# HV_DAC_8ch_References.net
KiCad netlist of a schematic drawn in Altium Designer
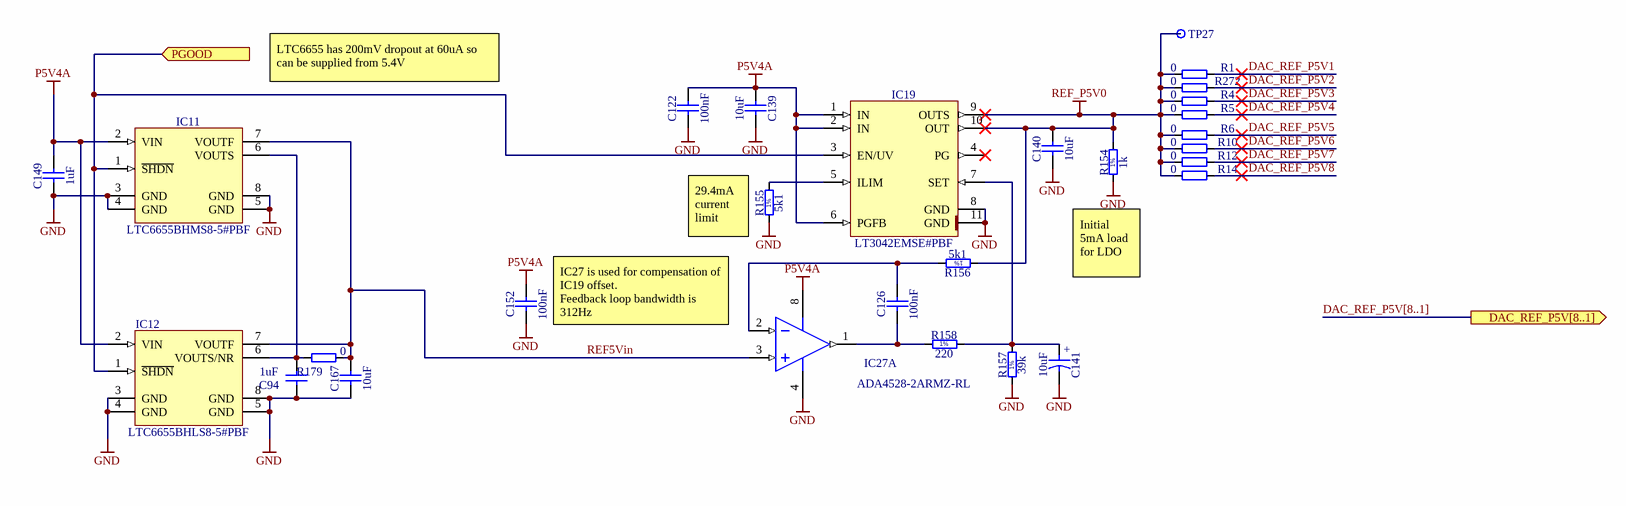
[diagram p0: HV_DAC_8ch_References.SchDoc]

(export (version "E")
  (design (tool "Eeschema 10.0.6"))
  (components
    (comp (ref "C94")
      (value "1uF")
      (footprint "CAPC1608X87N")
      (description "Non-polarised capacitor")
      (fields
        (field (name "PART NUMBER") "CC0603_1UF_25V_10%_X7R")
        (field (name "VOLTAGE") "25V")
        (field (name "AUTHOR") "CERN DEM JLC")
      )
      (libsource (lib "Capacitors") (part "Capacitor - non polarized"))
    )
    (comp (ref "C122")
      (value "100nF")
      (footprint "CAPC1005X55N")
      (description "Non-polarised capacitor")
      (fields
        (field (name "PART NUMBER") "CC0402_100NF_16V_10%_X5R")
        (field (name "VOLTAGE") "16V")
        (field (name "AUTHOR") "CERN DEM JLC")
      )
      (libsource (lib "Capacitors") (part "Capacitor - non polarized"))
    )
    (comp (ref "C126")
      (value "100nF")
      (footprint "CAPC1005X55N")
      (description "Non-polarised capacitor")
      (fields
        (field (name "PART NUMBER") "CC0402_100NF_16V_10%_X5R")
        (field (name "VOLTAGE") "16V")
        (field (name "AUTHOR") "CERN DEM JLC")
      )
      (libsource (lib "Capacitors") (part "Capacitor - non polarized"))
    )
    (comp (ref "C139")
      (value "10uF")
      (footprint "CAPC1608X80N")
      (description "Non-polarised capacitor")
      (fields
        (field (name "PART NUMBER") "CC0603_10UF_10V_10%_X5R")
        (field (name "VOLTAGE") "10V")
        (field (name "AUTHOR") "CERN DEM JLC")
      )
      (libsource (lib "Capacitors") (part "Capacitor - non polarized"))
    )
    (comp (ref "C140")
      (value "10uF")
      (footprint "CAPC1608X80N")
      (description "Non-polarised capacitor")
      (fields
        (field (name "PART NUMBER") "CC0603_10UF_10V_10%_X5R")
        (field (name "VOLTAGE") "10V")
        (field (name "AUTHOR") "CERN DEM JLC")
      )
      (libsource (lib "Capacitors") (part "Capacitor - non polarized"))
    )
    (comp (ref "C141")
      (value "10uF")
      (footprint "CAPMP3216X180N")
      (description "Polarised capacitor")
      (fields
        (field (name "PART NUMBER") "CTE3216-18_10UF_16V_20%_AVX_TCJ")
        (field (name "VOLTAGE") "16V")
        (field (name "AUTHOR") "CERN DEM JLC")
      )
      (libsource (lib "Capacitors") (part "Capacitor - polarized"))
    )
    (comp (ref "C149")
      (value "1uF")
      (footprint "CAPC1608X87N")
      (description "Non-polarised capacitor")
      (fields
        (field (name "PART NUMBER") "CC0603_1UF_25V_10%_X7R")
        (field (name "VOLTAGE") "25V")
        (field (name "AUTHOR") "CERN DEM JLC")
      )
      (libsource (lib "Capacitors") (part "Capacitor - non polarized"))
    )
    (comp (ref "C152")
      (value "100nF")
      (footprint "CAPC1005X55N")
      (description "Non-polarised capacitor")
      (fields
        (field (name "PART NUMBER") "CC0402_100NF_16V_10%_X5R")
        (field (name "VOLTAGE") "16V")
        (field (name "AUTHOR") "CERN DEM JLC")
      )
      (libsource (lib "Capacitors") (part "Capacitor - non polarized"))
    )
    (comp (ref "C167")
      (value "10uF")
      (footprint "CAPC1608X80N")
      (description "Non-polarised capacitor")
      (fields
        (field (name "PART NUMBER") "CC0603_10UF_10V_10%_X5R")
        (field (name "VOLTAGE") "10V")
        (field (name "AUTHOR") "CERN DEM JLC")
      )
      (libsource (lib "Capacitors") (part "Capacitor - non polarized"))
    )
    (comp (ref "IC11")
      (value "LTC6655BHMS8-5#PBF")
      (footprint "SOP65P490X110-8N")
      (description "0.25ppm Noise, Low Drift Precision Buffered Voltage Reference")
      (fields (field (name "MANUFACTURER") "LINEAR TECHNOLOGY") (field (name "AUTHOR") "CERN DEM JLC"))
      (libsource (lib "ICs And Semiconductors") (part "LTC6655"))
    )
    (comp (ref "IC12")
      (value "LTC6655BHLS8-5#PBF")
      (footprint "8-CLCC")
      (description "5.0V, 1uA Precision Voltage Reference")
      (fields (field (name "MANUFACTURER") "LINEAR TECHNOLOGY") (field (name "AUTHOR") "GK"))
      (libsource (lib "Sampler") (part "REF_LTC6655CHLS8-4.096"))
    )
    (comp (ref "IC19")
      (value "LT3042EMSE#PBF")
      (footprint "SOP50P490X110-11N-R168X198")
      (description "20V, 200mA, Ultralow Noise, Ultrahigh PSRR RF Linear Regulator")
      (fields (field (name "MANUFACTURER") "LINEAR TECHNOLOGY") (field (name "AUTHOR") "CERN DEM MR"))
      (libsource (lib "ICs And Semiconductors") (part "LT3042"))
    )
    (comp (ref "IC27")
      (value "ADA4528-2ARMZ-RL")
      (footprint "ADI-RM-8_N")
      (fields (field (name "GENERIC PART NUMBER") "ADA4528-2") (field (name "MANUFACTURER") "Analog Devices"))
      (libsource (lib "Altium Content Vault") (part "ADI-ADA4000-2-X-8"))
    )
    (comp (ref "R1")
      (value "0")
      (footprint "RESC1005X40N")
      (description "Resistor")
      (fields
        (field (name "PART NUMBER") "R0402_0R_JUMPER")
        (field (name "MANUFACTURER") "GENERIC")
        (field (name "AUTHOR") "CERN DEM JLC")
      )
      (libsource (lib "Resistors") (part "Resistor"))
    )
    (comp (ref "R4")
      (value "0")
      (footprint "RESC1005X40N")
      (description "Resistor")
      (fields
        (field (name "PART NUMBER") "R0402_0R_JUMPER")
        (field (name "MANUFACTURER") "GENERIC")
        (field (name "AUTHOR") "CERN DEM JLC")
      )
      (libsource (lib "Resistors") (part "Resistor"))
    )
    (comp (ref "R5")
      (value "0")
      (footprint "RESC1005X40N")
      (description "Resistor")
      (fields
        (field (name "PART NUMBER") "R0402_0R_JUMPER")
        (field (name "MANUFACTURER") "GENERIC")
        (field (name "AUTHOR") "CERN DEM JLC")
      )
      (libsource (lib "Resistors") (part "Resistor"))
    )
    (comp (ref "R6")
      (value "0")
      (footprint "RESC1005X40N")
      (description "Resistor")
      (fields
        (field (name "PART NUMBER") "R0402_0R_JUMPER")
        (field (name "MANUFACTURER") "GENERIC")
        (field (name "AUTHOR") "CERN DEM JLC")
      )
      (libsource (lib "Resistors") (part "Resistor"))
    )
    (comp (ref "R10")
      (value "0")
      (footprint "RESC1005X40N")
      (description "Resistor")
      (fields
        (field (name "PART NUMBER") "R0402_0R_JUMPER")
        (field (name "MANUFACTURER") "GENERIC")
        (field (name "AUTHOR") "CERN DEM JLC")
      )
      (libsource (lib "Resistors") (part "Resistor"))
    )
    (comp (ref "R12")
      (value "0")
      (footprint "RESC1005X40N")
      (description "Resistor")
      (fields
        (field (name "PART NUMBER") "R0402_0R_JUMPER")
        (field (name "MANUFACTURER") "GENERIC")
        (field (name "AUTHOR") "CERN DEM JLC")
      )
      (libsource (lib "Resistors") (part "Resistor"))
    )
    (comp (ref "R14")
      (value "0")
      (footprint "RESC1005X40N")
      (description "Resistor")
      (fields
        (field (name "PART NUMBER") "R0402_0R_JUMPER")
        (field (name "MANUFACTURER") "GENERIC")
        (field (name "AUTHOR") "CERN DEM JLC")
      )
      (libsource (lib "Resistors") (part "Resistor"))
    )
    (comp (ref "R154")
      (value "1k")
      (footprint "RESC1005X40N")
      (description "Resistor - 1%")
      (fields
        (field (name "PART NUMBER") "R0402_1K_1%_0.0625W_100PPM")
        (field (name "POWER") "0.0625W")
        (field (name "AUTHOR") "CERN DEM JLC")
      )
      (libsource (lib "Resistors") (part "Resistor - 1%"))
    )
    (comp (ref "R155")
      (value "5k1")
      (footprint "RESC1005X40N")
      (description "Resistor - 1%")
      (fields
        (field (name "PART NUMBER") "R0402_5K1_1%_0.0625W_100PPM")
        (field (name "POWER") "0.0625W")
        (field (name "AUTHOR") "CERN DEM JLC")
      )
      (libsource (lib "Resistors") (part "Resistor - 1%"))
    )
    (comp (ref "R156")
      (value "5k1")
      (footprint "RESC1005X40N")
      (description "Resistor - 1%")
      (fields
        (field (name "PART NUMBER") "R0402_5K1_1%_0.0625W_100PPM")
        (field (name "POWER") "0.0625W")
        (field (name "AUTHOR") "CERN DEM JLC")
      )
      (libsource (lib "Resistors") (part "Resistor - 1%"))
    )
    (comp (ref "R157")
      (value "39k")
      (footprint "RESC1608X55N")
      (description "Resistor - 1%")
      (fields
        (field (name "PART NUMBER") "R0603_39K_1%_0.1W_100PPM")
        (field (name "POWER") "0.1W")
        (field (name "AUTHOR") "CERN DEM JLC")
      )
      (libsource (lib "Resistors") (part "Resistor - 1%"))
    )
    (comp (ref "R158")
      (value "220")
      (footprint "RESC1005X40N")
      (description "Resistor - 1%")
      (fields
        (field (name "PART NUMBER") "R0402_220R_1%_0.0625W_100PPM")
        (field (name "POWER") "0.0625W")
        (field (name "AUTHOR") "CERN DEM JLC")
      )
      (libsource (lib "Resistors") (part "Resistor - 1%"))
    )
    (comp (ref "R179")
      (value "0")
      (footprint "RESC1005X40N")
      (description "Resistor")
      (fields
        (field (name "PART NUMBER") "R0402_0R_JUMPER")
        (field (name "MANUFACTURER") "GENERIC")
        (field (name "AUTHOR") "CERN DEM JLC")
      )
      (libsource (lib "Resistors") (part "Resistor"))
    )
    (comp (ref "R272")
      (value "0")
      (footprint "RESC1005X40N")
      (description "Resistor")
      (fields
        (field (name "PART NUMBER") "R0402_0R_JUMPER")
        (field (name "MANUFACTURER") "GENERIC")
        (field (name "AUTHOR") "CERN DEM JLC")
      )
      (libsource (lib "Resistors") (part "Resistor"))
    )
    (comp (ref "TP27")
      (value "Test Point")
      (footprint "TPS127")
      (fields (field (name "PART NUMBER") "SMD_PAD_1.27X1.27MM") (field (name "AUTHOR") "CERN DEM JLC"))
      (libsource (lib "Eletro-mechanical") (part "Test Point"))
    )
  )
  (nets
    (net (code "1") (name "/DAC_REF_P5V1") (class "Default")
      (node (ref "R1") (pin "2") (pinfunction "2_2") (pintype "passive"))
    )
    (net (code "2") (name "/DAC_REF_P5V2") (class "Default")
      (node (ref "R272") (pin "2") (pinfunction "2_2") (pintype "passive"))
    )
    (net (code "3") (name "/DAC_REF_P5V3") (class "Default")
      (node (ref "R4") (pin "2") (pinfunction "2_2") (pintype "passive"))
    )
    (net (code "4") (name "/DAC_REF_P5V4") (class "Default")
      (node (ref "R5") (pin "2") (pinfunction "2_2") (pintype "passive"))
    )
    (net (code "5") (name "/DAC_REF_P5V5") (class "Default")
      (node (ref "R6") (pin "2") (pinfunction "2_2") (pintype "passive"))
    )
    (net (code "6") (name "/DAC_REF_P5V6") (class "Default")
      (node (ref "R10") (pin "2") (pinfunction "2_2") (pintype "passive"))
    )
    (net (code "7") (name "/DAC_REF_P5V7") (class "Default")
      (node (ref "R12") (pin "2") (pinfunction "2_2") (pintype "passive"))
    )
    (net (code "8") (name "/DAC_REF_P5V8") (class "Default")
      (node (ref "R14") (pin "2") (pinfunction "2_2") (pintype "passive"))
    )
    (net (code "10") (name "/PGOOD") (class "Default")
      (node (ref "IC11") (pin "1") (pinfunction "~{SHDN}_1") (pintype "input"))
      (node (ref "IC12") (pin "1") (pinfunction "~{SHDN}_1") (pintype "input"))
      (node (ref "IC19") (pin "3") (pinfunction "EN/UV_3") (pintype "input"))
    )
    (net (code "11") (name "/REF5Vin") (class "Default")
      (node (ref "C167") (pin "2") (pinfunction "2_2") (pintype "passive"))
      (node (ref "IC11") (pin "7") (pinfunction "VOUTF_7") (pintype "power_in"))
      (node (ref "IC12") (pin "7") (pinfunction "VOUTF_7") (pintype "power_in"))
      (node (ref "IC27") (pin "3") (pinfunction "+IN_A_3") (pintype "input"))
      (node (ref "R179") (pin "2") (pinfunction "2_2") (pintype "passive"))
    )
    (net (code "12") (name "GND") (class "Default")
      (node (ref "C122") (pin "1") (pinfunction "1_1") (pintype "passive"))
      (node (ref "C139") (pin "2") (pinfunction "2_2") (pintype "passive"))
      (node (ref "C140") (pin "1") (pinfunction "1_1") (pintype "passive"))
      (node (ref "C141") (pin "2") (pinfunction "2_2") (pintype "passive"))
      (node (ref "C149") (pin "1") (pinfunction "1_1") (pintype "passive"))
      (node (ref "C152") (pin "1") (pinfunction "1_1") (pintype "passive"))
      (node (ref "C167") (pin "1") (pinfunction "1_1") (pintype "passive"))
      (node (ref "C94") (pin "1") (pinfunction "1_1") (pintype "passive"))
      (node (ref "IC11") (pin "3") (pinfunction "GND_3") (pintype "power_in"))
      (node (ref "IC11") (pin "4") (pinfunction "GND_4") (pintype "power_in"))
      (node (ref "IC11") (pin "5") (pinfunction "GND_5") (pintype "power_in"))
      (node (ref "IC11") (pin "8") (pinfunction "GND_8") (pintype "power_in"))
      (node (ref "IC12") (pin "3") (pinfunction "GND_3") (pintype "power_in"))
      (node (ref "IC12") (pin "4") (pinfunction "GND_4") (pintype "power_in"))
      (node (ref "IC12") (pin "5") (pinfunction "GND_5") (pintype "power_in"))
      (node (ref "IC12") (pin "8") (pinfunction "GND_8") (pintype "power_in"))
      (node (ref "IC19") (pin "11") (pinfunction "GND_11") (pintype "power_in"))
      (node (ref "IC19") (pin "8") (pinfunction "GND_8") (pintype "power_in"))
      (node (ref "IC27") (pin "4") (pinfunction "-V_4") (pintype "power_in"))
      (node (ref "R154") (pin "1") (pinfunction "1_1") (pintype "passive"))
      (node (ref "R155") (pin "1") (pinfunction "1_1") (pintype "passive"))
      (node (ref "R157") (pin "1") (pinfunction "1_1") (pintype "passive"))
    )
    (net (code "13") (name "Net-(IC11-VOUTS)") (class "Default")
      (node (ref "C94") (pin "2") (pinfunction "2_2") (pintype "passive"))
      (node (ref "IC11") (pin "6") (pinfunction "VOUTS_6") (pintype "power_in"))
      (node (ref "IC12") (pin "6") (pinfunction "VOUTS/NR_6") (pintype "power_in"))
      (node (ref "R179") (pin "1") (pinfunction "1_1") (pintype "passive"))
    )
    (net (code "14") (name "Net-(IC19-ILIM)") (class "Default")
      (node (ref "IC19") (pin "5") (pinfunction "ILIM_5") (pintype "input"))
      (node (ref "R155") (pin "2") (pinfunction "2_2") (pintype "passive"))
    )
    (net (code "15") (name "Net-(IC19-SET)") (class "Default")
      (node (ref "C141") (pin "1") (pinfunction "1_1") (pintype "passive"))
      (node (ref "IC19") (pin "7") (pinfunction "SET_7") (pintype "input"))
      (node (ref "R157") (pin "2") (pinfunction "2_2") (pintype "passive"))
      (node (ref "R158") (pin "2") (pinfunction "2_2") (pintype "passive"))
    )
    (net (code "16") (name "Net-(IC27A--IN_A)") (class "Default")
      (node (ref "C126") (pin "2") (pinfunction "2_2") (pintype "passive"))
      (node (ref "IC27") (pin "2") (pinfunction "-IN_A_2") (pintype "input"))
      (node (ref "R156") (pin "2") (pinfunction "2_2") (pintype "passive"))
    )
    (net (code "17") (name "Net-(IC27A-OUT_A)") (class "Default")
      (node (ref "C126") (pin "1") (pinfunction "1_1") (pintype "passive"))
      (node (ref "IC27") (pin "1") (pinfunction "OUT_A_1") (pintype "output"))
      (node (ref "R158") (pin "1") (pinfunction "1_1") (pintype "passive"))
    )
    (net (code "18") (name "P5V4A") (class "Default")
      (node (ref "C122") (pin "2") (pinfunction "2_2") (pintype "passive"))
      (node (ref "C139") (pin "1") (pinfunction "1_1") (pintype "passive"))
      (node (ref "C149") (pin "2") (pinfunction "2_2") (pintype "passive"))
      (node (ref "C152") (pin "2") (pinfunction "2_2") (pintype "passive"))
      (node (ref "IC11") (pin "2") (pinfunction "VIN_2") (pintype "input"))
      (node (ref "IC12") (pin "2") (pinfunction "VIN_2") (pintype "input"))
      (node (ref "IC19") (pin "1") (pinfunction "IN_1") (pintype "input"))
      (node (ref "IC19") (pin "2") (pinfunction "IN_2") (pintype "input"))
      (node (ref "IC19") (pin "6") (pinfunction "PGFB_6") (pintype "input"))
      (node (ref "IC27") (pin "8") (pinfunction "+V_8") (pintype "power_in"))
    )
    (net (code "19") (name "REF_P5V0") (class "Default")
      (node (ref "C140") (pin "2") (pinfunction "2_2") (pintype "passive"))
      (node (ref "IC19") (pin "10") (pinfunction "OUT_10") (pintype "output"))
      (node (ref "IC19") (pin "9") (pinfunction "OUTS_9") (pintype "output"))
      (node (ref "R1") (pin "1") (pinfunction "1_1") (pintype "passive"))
      (node (ref "R10") (pin "1") (pinfunction "1_1") (pintype "passive"))
      (node (ref "R12") (pin "1") (pinfunction "1_1") (pintype "passive"))
      (node (ref "R14") (pin "1") (pinfunction "1_1") (pintype "passive"))
      (node (ref "R154") (pin "2") (pinfunction "2_2") (pintype "passive"))
      (node (ref "R156") (pin "1") (pinfunction "1_1") (pintype "passive"))
      (node (ref "R272") (pin "1") (pinfunction "1_1") (pintype "passive"))
      (node (ref "R4") (pin "1") (pinfunction "1_1") (pintype "passive"))
      (node (ref "R5") (pin "1") (pinfunction "1_1") (pintype "passive"))
      (node (ref "R6") (pin "1") (pinfunction "1_1") (pintype "passive"))
      (node (ref "TP27") (pin "1") (pinfunction "1_1") (pintype "bidirectional"))
    )
    (net (code "20") (name "unconnected-(IC19-PG-Pad4)") (class "Default")
      (node (ref "IC19") (pin "4") (pinfunction "PG_4") (pintype "output+no_connect"))
    )
  )
)
